# support.net
KiCad netlist of a schematic drawn in Altium Designer
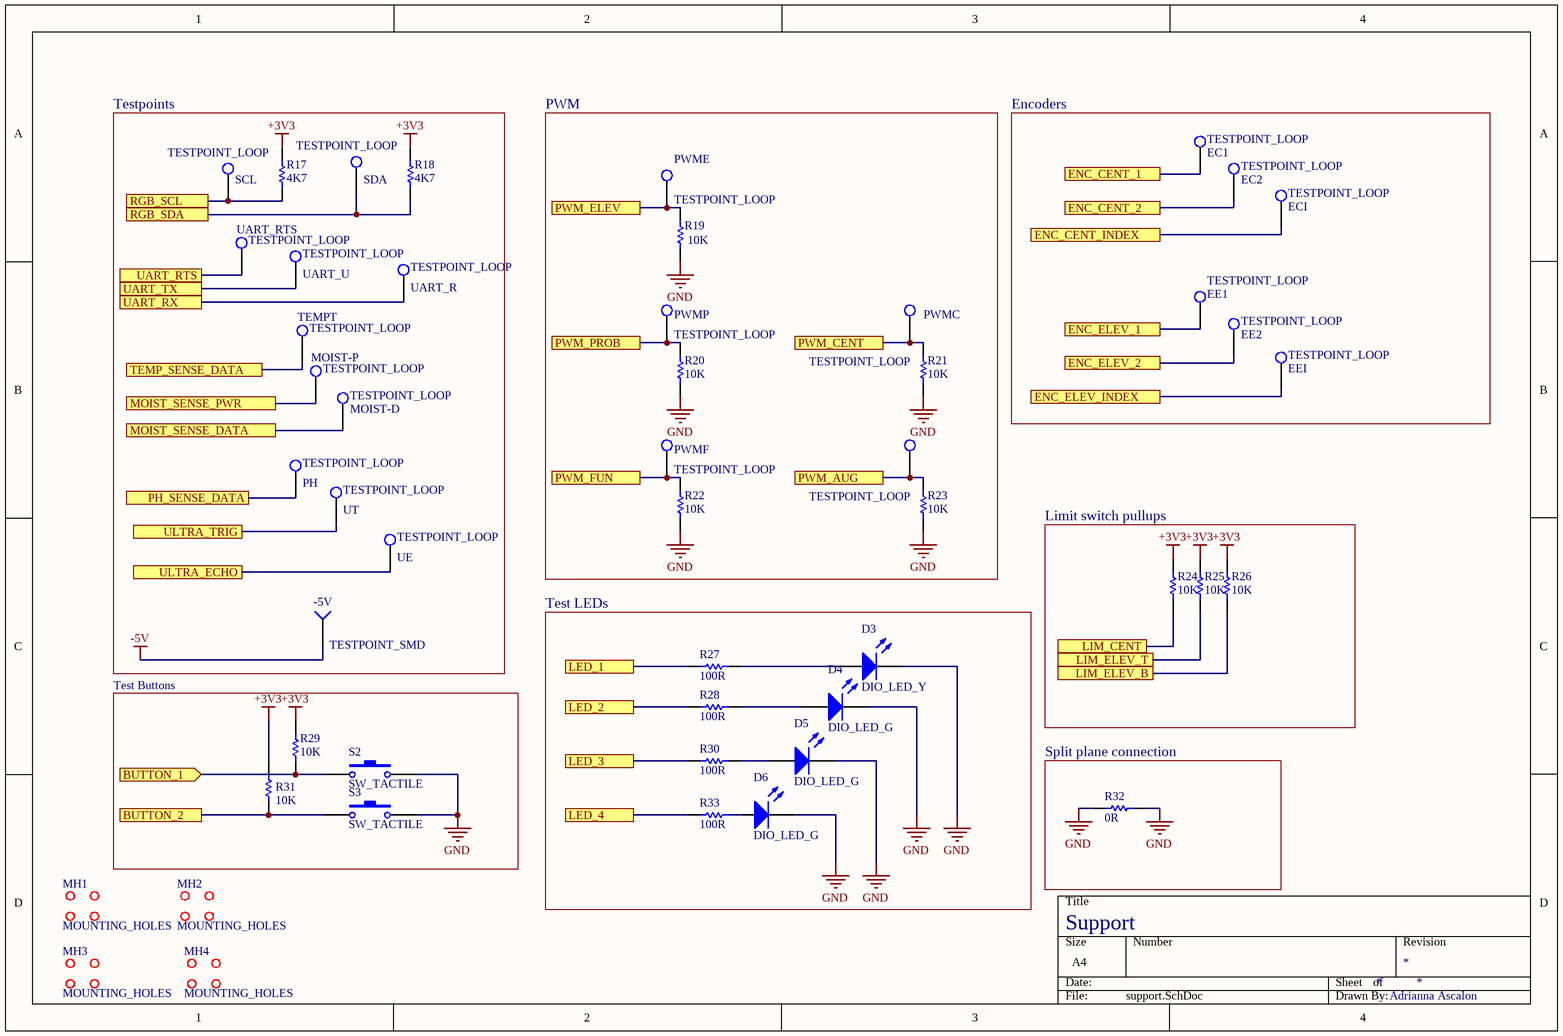
[diagram p0: support.SchDoc]

(export (version "E")
  (design (tool "Eeschema 10.0.6"))
  (components
    (comp (ref "-5V")
      (value "TESTPOINT_SMD")
      (footprint "TESTPOINT")
      (libsource (lib "UWRT_Schematic_Library_2019") (part "TESTPOINT_SMD"))
    )
    (comp (ref "D3")
      (value "DIO_LED_Y")
      (footprint "LED_0805_LINE")
      (description "LED YELLOW DIFFUSED 0805 SMD")
      (fields (field (name "MANUFACTURER") "OSRAM") (field (name "MPN") "LY R976-PS-36"))
      (libsource (lib "UWRT_Schematic_Library_2019") (part "DIO_LED_Y"))
    )
    (comp (ref "D4")
      (value "DIO_LED_G")
      (footprint "LED_0805_LINE")
      (description "LED GREEN DIFFUSED 0805 SMD")
      (fields (field (name "MANUFACTURER") "OSRAM") (field (name "MPN") "LG R971-KN-1"))
      (libsource (lib "UWRT_Schematic_Library_2019") (part "DIO_LED_G"))
    )
    (comp (ref "D5")
      (value "DIO_LED_G")
      (footprint "LED_0805_LINE")
      (description "LED GREEN DIFFUSED 0805 SMD")
      (fields (field (name "MANUFACTURER") "OSRAM") (field (name "MPN") "LG R971-KN-1"))
      (libsource (lib "UWRT_Schematic_Library_2019") (part "DIO_LED_G"))
    )
    (comp (ref "D6")
      (value "DIO_LED_G")
      (footprint "LED_0805_LINE")
      (description "LED GREEN DIFFUSED 0805 SMD")
      (fields (field (name "MANUFACTURER") "OSRAM") (field (name "MPN") "LG R971-KN-1"))
      (libsource (lib "UWRT_Schematic_Library_2019") (part "DIO_LED_G"))
    )
    (comp (ref "EC1")
      (value "TESTPOINT_LOOP")
      (footprint "TESTPOINT_LOOP")
      (libsource (lib "UWRT_Schematic_Library_2019") (part "TESTPOINT_LOOP"))
    )
    (comp (ref "EC2")
      (value "TESTPOINT_LOOP")
      (footprint "TESTPOINT_LOOP")
      (libsource (lib "UWRT_Schematic_Library_2019") (part "TESTPOINT_LOOP"))
    )
    (comp (ref "ECI")
      (value "TESTPOINT_LOOP")
      (footprint "TESTPOINT_LOOP")
      (libsource (lib "UWRT_Schematic_Library_2019") (part "TESTPOINT_LOOP"))
    )
    (comp (ref "EE1")
      (value "TESTPOINT_LOOP")
      (footprint "TESTPOINT_LOOP")
      (libsource (lib "UWRT_Schematic_Library_2019") (part "TESTPOINT_LOOP"))
    )
    (comp (ref "EE2")
      (value "TESTPOINT_LOOP")
      (footprint "TESTPOINT_LOOP")
      (libsource (lib "UWRT_Schematic_Library_2019") (part "TESTPOINT_LOOP"))
    )
    (comp (ref "EEI")
      (value "TESTPOINT_LOOP")
      (footprint "TESTPOINT_LOOP")
      (libsource (lib "UWRT_Schematic_Library_2019") (part "TESTPOINT_LOOP"))
    )
    (comp (ref "MH1")
      (value "MOUNTING_HOLES")
      (footprint "MOUNTING_HOLE")
      (description "6cm x 6cm")
      (libsource (lib "UWRT_Schematic_Library_2019") (part "MOUNTING_HOLES"))
    )
    (comp (ref "MH2")
      (value "MOUNTING_HOLES")
      (footprint "MOUNTING_HOLE")
      (description "6cm x 6cm")
      (libsource (lib "UWRT_Schematic_Library_2019") (part "MOUNTING_HOLES"))
    )
    (comp (ref "MH3")
      (value "MOUNTING_HOLES")
      (footprint "MOUNTING_HOLE")
      (description "6cm x 6cm")
      (libsource (lib "UWRT_Schematic_Library_2019") (part "MOUNTING_HOLES"))
    )
    (comp (ref "MH4")
      (value "MOUNTING_HOLES")
      (footprint "MOUNTING_HOLE")
      (description "6cm x 6cm")
      (libsource (lib "UWRT_Schematic_Library_2019") (part "MOUNTING_HOLES"))
    )
    (comp (ref "MOIST-D")
      (value "TESTPOINT_LOOP")
      (footprint "TESTPOINT_LOOP")
      (libsource (lib "UWRT_Schematic_Library_2019") (part "TESTPOINT_LOOP"))
    )
    (comp (ref "MOIST-P")
      (value "TESTPOINT_LOOP")
      (footprint "TESTPOINT_LOOP")
      (libsource (lib "UWRT_Schematic_Library_2019") (part "TESTPOINT_LOOP"))
    )
    (comp (ref "PH")
      (value "TESTPOINT_LOOP")
      (footprint "TESTPOINT_LOOP")
      (libsource (lib "UWRT_Schematic_Library_2019") (part "TESTPOINT_LOOP"))
    )
    (comp (ref "PWMA")
      (value "TESTPOINT_LOOP")
      (footprint "TESTPOINT_LOOP")
      (libsource (lib "UWRT_Schematic_Library_2019") (part "TESTPOINT_LOOP"))
    )
    (comp (ref "PWMC")
      (value "TESTPOINT_LOOP")
      (footprint "TESTPOINT_LOOP")
      (libsource (lib "UWRT_Schematic_Library_2019") (part "TESTPOINT_LOOP"))
    )
    (comp (ref "PWME")
      (value "TESTPOINT_LOOP")
      (footprint "TESTPOINT_LOOP")
      (libsource (lib "UWRT_Schematic_Library_2019") (part "TESTPOINT_LOOP"))
    )
    (comp (ref "PWMF")
      (value "TESTPOINT_LOOP")
      (footprint "TESTPOINT_LOOP")
      (libsource (lib "UWRT_Schematic_Library_2019") (part "TESTPOINT_LOOP"))
    )
    (comp (ref "PWMP")
      (value "TESTPOINT_LOOP")
      (footprint "TESTPOINT_LOOP")
      (libsource (lib "UWRT_Schematic_Library_2019") (part "TESTPOINT_LOOP"))
    )
    (comp (ref "R17")
      (value "4K7")
      (footprint "RESC0603(1608)_N")
      (description "RES SMD 4.7K OHM 5% 1/10W 0603")
      (fields (field (name "MANUFACTURER") "Yageo") (field (name "TOLERANCE") "5%"))
      (libsource (lib "UWRT_Schematic_Library_2019") (part "RES_4K7_0603"))
    )
    (comp (ref "R18")
      (value "4K7")
      (footprint "RESC0603(1608)_N")
      (description "RES SMD 4.7K OHM 5% 1/10W 0603")
      (fields (field (name "MANUFACTURER") "Yageo") (field (name "TOLERANCE") "5%"))
      (libsource (lib "UWRT_Schematic_Library_2019") (part "RES_4K7_0603"))
    )
    (comp (ref "R19")
      (value "10K")
      (footprint "RESC0603(1608)_N")
      (description "RES SMD 10K OHM 5% 1/10W 0603")
      (fields (field (name "MANUFACTURER") "Yageo") (field (name "TOLERANCE") "5%"))
      (libsource (lib "UWRT_Schematic_Library_2019") (part "RES_10K_0603"))
    )
    (comp (ref "R20")
      (value "10K")
      (footprint "RESC0603(1608)_N")
      (description "RES SMD 10K OHM 5% 1/10W 0603")
      (fields (field (name "MANUFACTURER") "Yageo") (field (name "TOLERANCE") "5%"))
      (libsource (lib "UWRT_Schematic_Library_2019") (part "RES_10K_0603"))
    )
    (comp (ref "R21")
      (value "10K")
      (footprint "RESC0603(1608)_N")
      (description "RES SMD 10K OHM 5% 1/10W 0603")
      (fields (field (name "MANUFACTURER") "Yageo") (field (name "TOLERANCE") "5%"))
      (libsource (lib "UWRT_Schematic_Library_2019") (part "RES_10K_0603"))
    )
    (comp (ref "R22")
      (value "10K")
      (footprint "RESC0603(1608)_N")
      (description "RES SMD 10K OHM 5% 1/10W 0603")
      (fields (field (name "MANUFACTURER") "Yageo") (field (name "TOLERANCE") "5%"))
      (libsource (lib "UWRT_Schematic_Library_2019") (part "RES_10K_0603"))
    )
    (comp (ref "R23")
      (value "10K")
      (footprint "RESC0603(1608)_N")
      (description "RES SMD 10K OHM 5% 1/10W 0603")
      (fields (field (name "MANUFACTURER") "Yageo") (field (name "TOLERANCE") "5%"))
      (libsource (lib "UWRT_Schematic_Library_2019") (part "RES_10K_0603"))
    )
    (comp (ref "R24")
      (value "10K")
      (footprint "RESC0603(1608)_N")
      (description "RES SMD 10K OHM 5% 1/10W 0603")
      (fields (field (name "MANUFACTURER") "Yageo") (field (name "TOLERANCE") "5%"))
      (libsource (lib "UWRT_Schematic_Library_2019") (part "RES_10K_0603"))
    )
    (comp (ref "R25")
      (value "10K")
      (footprint "RESC0603(1608)_N")
      (description "RES SMD 10K OHM 5% 1/10W 0603")
      (fields (field (name "MANUFACTURER") "Yageo") (field (name "TOLERANCE") "5%"))
      (libsource (lib "UWRT_Schematic_Library_2019") (part "RES_10K_0603"))
    )
    (comp (ref "R26")
      (value "10K")
      (footprint "RESC0603(1608)_N")
      (description "RES SMD 10K OHM 5% 1/10W 0603")
      (fields (field (name "MANUFACTURER") "Yageo") (field (name "TOLERANCE") "5%"))
      (libsource (lib "UWRT_Schematic_Library_2019") (part "RES_10K_0603"))
    )
    (comp (ref "R27")
      (value "100R")
      (footprint "RESC0603(1608)_N")
      (description "RES SMD 100 OHM 1% 1/10W 0603")
      (fields (field (name "MANUFACTURER") "Yageo") (field (name "TOLERANCE") "1%"))
      (libsource (lib "UWRT_Schematic_Library_2019") (part "RES_100R_0603"))
    )
    (comp (ref "R28")
      (value "100R")
      (footprint "RESC0603(1608)_N")
      (description "RES SMD 100 OHM 1% 1/10W 0603")
      (fields (field (name "MANUFACTURER") "Yageo") (field (name "TOLERANCE") "1%"))
      (libsource (lib "UWRT_Schematic_Library_2019") (part "RES_100R_0603"))
    )
    (comp (ref "R29")
      (value "10K")
      (footprint "RESC0603(1608)_N")
      (description "RES SMD 10K OHM 5% 1/10W 0603")
      (fields (field (name "MANUFACTURER") "Yageo") (field (name "TOLERANCE") "5%"))
      (libsource (lib "UWRT_Schematic_Library_2019") (part "RES_10K_0603"))
    )
    (comp (ref "R30")
      (value "100R")
      (footprint "RESC0603(1608)_N")
      (description "RES SMD 100 OHM 1% 1/10W 0603")
      (fields (field (name "MANUFACTURER") "Yageo") (field (name "TOLERANCE") "1%"))
      (libsource (lib "UWRT_Schematic_Library_2019") (part "RES_100R_0603"))
    )
    (comp (ref "R31")
      (value "10K")
      (footprint "RESC0603(1608)_N")
      (description "RES SMD 10K OHM 5% 1/10W 0603")
      (fields (field (name "MANUFACTURER") "Yageo") (field (name "TOLERANCE") "5%"))
      (libsource (lib "UWRT_Schematic_Library_2019") (part "RES_10K_0603"))
    )
    (comp (ref "R32")
      (value "0R")
      (footprint "RESC0603(1608)_N")
      (description "RES SMD 0 OHM JUMPER 1/10W 0603")
      (fields (field (name "MANUFACTURER") "Yageo") (field (name "MPN") "RC0603JR-070RL"))
      (libsource (lib "UWRT_Schematic_Library_2019") (part "RES_0R_0603"))
    )
    (comp (ref "R33")
      (value "100R")
      (footprint "RESC0603(1608)_N")
      (description "RES SMD 100 OHM 1% 1/10W 0603")
      (fields (field (name "MANUFACTURER") "Yageo") (field (name "TOLERANCE") "1%"))
      (libsource (lib "UWRT_Schematic_Library_2019") (part "RES_100R_0603"))
    )
    (comp (ref "S2")
      (value "SW_TACTILE")
      (footprint "B3U-1100P")
      (description "Tactile Switch (Grey)")
      (fields (field (name "DIGIKEY PART NUMBER") "SW1021TR-ND") (field (name "MPN") "B3U-1100P"))
      (libsource (lib "UWRT_Schematic_Library_2019") (part "SW_TACTILE"))
    )
    (comp (ref "S3")
      (value "SW_TACTILE")
      (footprint "B3U-1100P")
      (description "Tactile Switch (Grey)")
      (fields (field (name "DIGIKEY PART NUMBER") "SW1021TR-ND") (field (name "MPN") "B3U-1100P"))
      (libsource (lib "UWRT_Schematic_Library_2019") (part "SW_TACTILE"))
    )
    (comp (ref "SCL")
      (value "TESTPOINT_LOOP")
      (footprint "TESTPOINT_LOOP")
      (libsource (lib "UWRT_Schematic_Library_2019") (part "TESTPOINT_LOOP"))
    )
    (comp (ref "SDA")
      (value "TESTPOINT_LOOP")
      (footprint "TESTPOINT_LOOP")
      (libsource (lib "UWRT_Schematic_Library_2019") (part "TESTPOINT_LOOP"))
    )
    (comp (ref "TEMPT")
      (value "TESTPOINT_LOOP")
      (footprint "TESTPOINT_LOOP")
      (libsource (lib "UWRT_Schematic_Library_2019") (part "TESTPOINT_LOOP"))
    )
    (comp (ref "UART_R")
      (value "TESTPOINT_LOOP")
      (footprint "TESTPOINT_LOOP")
      (libsource (lib "UWRT_Schematic_Library_2019") (part "TESTPOINT_LOOP"))
    )
    (comp (ref "UART_RTS")
      (value "TESTPOINT_LOOP")
      (footprint "TESTPOINT_LOOP")
      (libsource (lib "UWRT_Schematic_Library_2019") (part "TESTPOINT_LOOP"))
    )
    (comp (ref "UART_U")
      (value "TESTPOINT_LOOP")
      (footprint "TESTPOINT_LOOP")
      (libsource (lib "UWRT_Schematic_Library_2019") (part "TESTPOINT_LOOP"))
    )
    (comp (ref "UE")
      (value "TESTPOINT_LOOP")
      (footprint "TESTPOINT_LOOP")
      (libsource (lib "UWRT_Schematic_Library_2019") (part "TESTPOINT_LOOP"))
    )
    (comp (ref "UT")
      (value "TESTPOINT_LOOP")
      (footprint "TESTPOINT_LOOP")
      (libsource (lib "UWRT_Schematic_Library_2019") (part "TESTPOINT_LOOP"))
    )
  )
  (nets
    (net (code "1") (name "+3V3") (class "Default")
      (node (ref "R17") (pin "2") (pinfunction "2_2") (pintype "passive"))
      (node (ref "R18") (pin "2") (pinfunction "2_2") (pintype "passive"))
      (node (ref "R24") (pin "2") (pinfunction "2_2") (pintype "passive"))
      (node (ref "R25") (pin "2") (pinfunction "2_2") (pintype "passive"))
      (node (ref "R26") (pin "2") (pinfunction "2_2") (pintype "passive"))
      (node (ref "R29") (pin "2") (pinfunction "2_2") (pintype "passive"))
      (node (ref "R31") (pin "1") (pinfunction "1_1") (pintype "passive"))
    )
    (net (code "2") (name "-5V") (class "Default")
      (node (ref "-5V") (pin "1") (pinfunction "=value_1") (pintype "passive"))
    )
    (net (code "3") (name "/BUTTON_1") (class "Default")
      (node (ref "R29") (pin "1") (pinfunction "1_1") (pintype "passive"))
      (node (ref "S2") (pin "1") (pinfunction "1_1") (pintype "passive"))
    )
    (net (code "4") (name "/BUTTON_2") (class "Default")
      (node (ref "R31") (pin "2") (pinfunction "2_2") (pintype "passive"))
      (node (ref "S3") (pin "1") (pinfunction "1_1") (pintype "passive"))
    )
    (net (code "5") (name "/ENC_CENT_1") (class "Default")
      (node (ref "EC1") (pin "1") (pinfunction "=value_1") (pintype "passive"))
    )
    (net (code "6") (name "/ENC_CENT_2") (class "Default")
      (node (ref "EC2") (pin "1") (pinfunction "=value_1") (pintype "passive"))
    )
    (net (code "7") (name "/ENC_CENT_INDEX") (class "Default")
      (node (ref "ECI") (pin "1") (pinfunction "=value_1") (pintype "passive"))
    )
    (net (code "8") (name "/ENC_ELEV_1") (class "Default")
      (node (ref "EE1") (pin "1") (pinfunction "=value_1") (pintype "passive"))
    )
    (net (code "9") (name "/ENC_ELEV_2") (class "Default")
      (node (ref "EE2") (pin "1") (pinfunction "=value_1") (pintype "passive"))
    )
    (net (code "10") (name "/ENC_ELEV_INDEX") (class "Default")
      (node (ref "EEI") (pin "1") (pinfunction "=value_1") (pintype "passive"))
    )
    (net (code "11") (name "/LED_1") (class "Default")
      (node (ref "R27") (pin "1") (pinfunction "1_1") (pintype "passive"))
    )
    (net (code "12") (name "/LED_2") (class "Default")
      (node (ref "R28") (pin "1") (pinfunction "1_1") (pintype "passive"))
    )
    (net (code "13") (name "/LED_3") (class "Default")
      (node (ref "R30") (pin "1") (pinfunction "1_1") (pintype "passive"))
    )
    (net (code "14") (name "/LED_4") (class "Default")
      (node (ref "R33") (pin "1") (pinfunction "1_1") (pintype "passive"))
    )
    (net (code "15") (name "/LIM_CENT") (class "Default")
      (node (ref "R24") (pin "1") (pinfunction "1_1") (pintype "passive"))
    )
    (net (code "16") (name "/LIM_ELEV_B") (class "Default")
      (node (ref "R26") (pin "1") (pinfunction "1_1") (pintype "passive"))
    )
    (net (code "17") (name "/LIM_ELEV_T") (class "Default")
      (node (ref "R25") (pin "1") (pinfunction "1_1") (pintype "passive"))
    )
    (net (code "18") (name "/MOIST_SENSE_DATA") (class "Default")
      (node (ref "MOIST-D") (pin "1") (pinfunction "=value_1") (pintype "passive"))
    )
    (net (code "19") (name "/MOIST_SENSE_PWR") (class "Default")
      (node (ref "MOIST-P") (pin "1") (pinfunction "=value_1") (pintype "passive"))
    )
    (net (code "20") (name "/PH_SENSE_DATA") (class "Default")
      (node (ref "PH") (pin "1") (pinfunction "=value_1") (pintype "passive"))
    )
    (net (code "21") (name "/PWM_AUG") (class "Default")
      (node (ref "PWMA") (pin "1") (pinfunction "=value_1") (pintype "passive"))
      (node (ref "R23") (pin "2") (pinfunction "2_2") (pintype "passive"))
    )
    (net (code "22") (name "/PWM_CENT") (class "Default")
      (node (ref "PWMC") (pin "1") (pinfunction "=value_1") (pintype "passive"))
      (node (ref "R21") (pin "2") (pinfunction "2_2") (pintype "passive"))
    )
    (net (code "23") (name "/PWM_ELEV") (class "Default")
      (node (ref "PWME") (pin "1") (pinfunction "=value_1") (pintype "passive"))
      (node (ref "R19") (pin "2") (pinfunction "2_2") (pintype "passive"))
    )
    (net (code "24") (name "/PWM_FUN") (class "Default")
      (node (ref "PWMF") (pin "1") (pinfunction "=value_1") (pintype "passive"))
      (node (ref "R22") (pin "2") (pinfunction "2_2") (pintype "passive"))
    )
    (net (code "25") (name "/PWM_PROB") (class "Default")
      (node (ref "PWMP") (pin "1") (pinfunction "=value_1") (pintype "passive"))
      (node (ref "R20") (pin "2") (pinfunction "2_2") (pintype "passive"))
    )
    (net (code "26") (name "/RGB_SCL") (class "Default")
      (node (ref "R17") (pin "1") (pinfunction "1_1") (pintype "passive"))
      (node (ref "SCL") (pin "1") (pinfunction "=value_1") (pintype "passive"))
    )
    (net (code "27") (name "/RGB_SDA") (class "Default")
      (node (ref "R18") (pin "1") (pinfunction "1_1") (pintype "passive"))
      (node (ref "SDA") (pin "1") (pinfunction "=value_1") (pintype "passive"))
    )
    (net (code "28") (name "/TEMP_SENSE_DATA") (class "Default")
      (node (ref "TEMPT") (pin "1") (pinfunction "=value_1") (pintype "passive"))
    )
    (net (code "29") (name "/UART_RTS") (class "Default")
      (node (ref "UART_RTS") (pin "1") (pinfunction "=value_1") (pintype "passive"))
    )
    (net (code "30") (name "/UART_RX") (class "Default")
      (node (ref "UART_R") (pin "1") (pinfunction "=value_1") (pintype "passive"))
    )
    (net (code "31") (name "/UART_TX") (class "Default")
      (node (ref "UART_U") (pin "1") (pinfunction "=value_1") (pintype "passive"))
    )
    (net (code "32") (name "/ULTRA_ECHO") (class "Default")
      (node (ref "UE") (pin "1") (pinfunction "=value_1") (pintype "passive"))
    )
    (net (code "33") (name "/ULTRA_TRIG") (class "Default")
      (node (ref "UT") (pin "1") (pinfunction "=value_1") (pintype "passive"))
    )
    (net (code "34") (name "GND") (class "Default")
      (node (ref "D3") (pin "2") (pinfunction "K_2") (pintype "passive"))
      (node (ref "D4") (pin "2") (pinfunction "K_2") (pintype "passive"))
      (node (ref "D5") (pin "2") (pinfunction "K_2") (pintype "passive"))
      (node (ref "D6") (pin "2") (pinfunction "K_2") (pintype "passive"))
      (node (ref "R19") (pin "1") (pinfunction "1_1") (pintype "passive"))
      (node (ref "R20") (pin "1") (pinfunction "1_1") (pintype "passive"))
      (node (ref "R21") (pin "1") (pinfunction "1_1") (pintype "passive"))
      (node (ref "R22") (pin "1") (pinfunction "1_1") (pintype "passive"))
      (node (ref "R23") (pin "1") (pinfunction "1_1") (pintype "passive"))
      (node (ref "R32") (pin "1") (pinfunction "1_1") (pintype "passive"))
      (node (ref "R32") (pin "2") (pinfunction "2_2") (pintype "passive"))
      (node (ref "S2") (pin "2") (pinfunction "2_2") (pintype "passive"))
      (node (ref "S3") (pin "2") (pinfunction "2_2") (pintype "passive"))
    )
    (net (code "35") (name "Net-(D3-A)") (class "Default")
      (node (ref "D3") (pin "1") (pinfunction "A_1") (pintype "passive"))
      (node (ref "R27") (pin "2") (pinfunction "2_2") (pintype "passive"))
    )
    (net (code "36") (name "Net-(D4-A)") (class "Default")
      (node (ref "D4") (pin "1") (pinfunction "A_1") (pintype "passive"))
      (node (ref "R28") (pin "2") (pinfunction "2_2") (pintype "passive"))
    )
    (net (code "37") (name "Net-(D5-A)") (class "Default")
      (node (ref "D5") (pin "1") (pinfunction "A_1") (pintype "passive"))
      (node (ref "R30") (pin "2") (pinfunction "2_2") (pintype "passive"))
    )
    (net (code "38") (name "Net-(D6-A)") (class "Default")
      (node (ref "D6") (pin "1") (pinfunction "A_1") (pintype "passive"))
      (node (ref "R33") (pin "2") (pinfunction "2_2") (pintype "passive"))
    )
  )
)
